# Dise_o_de_FISICA_v16.net
KiCad netlist of a schematic drawn in EAGLE
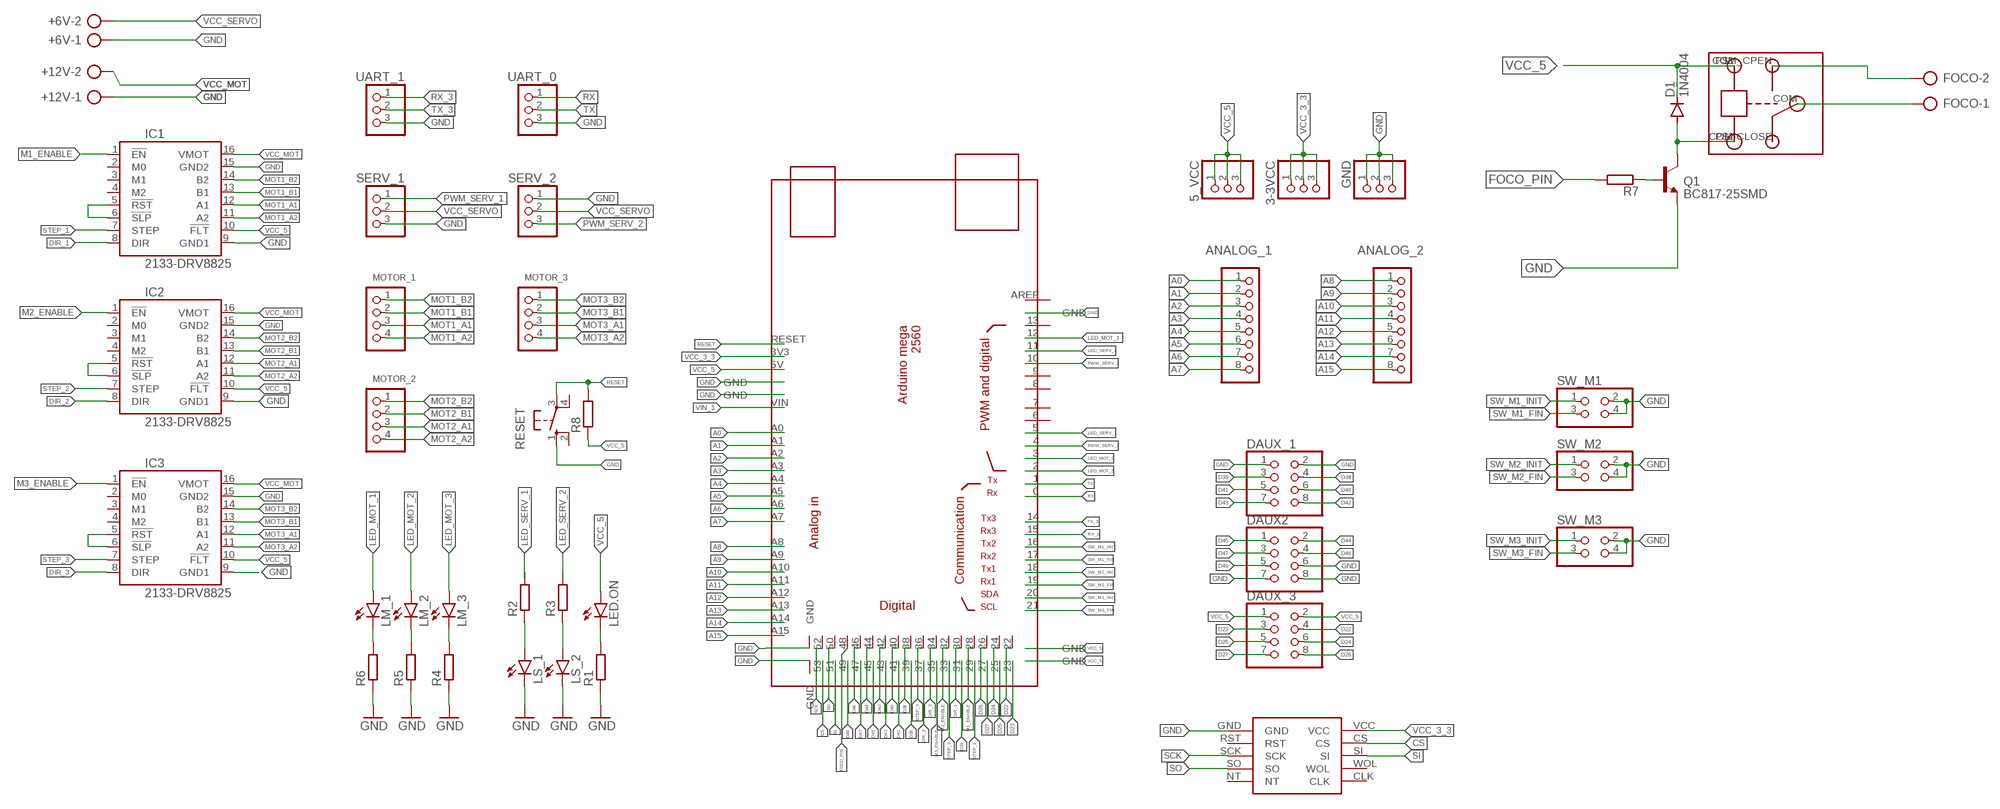
[diagram p0: schematic, sheet 1]

(export (version "E")
  (design (tool "Eeschema 10.0.6"))
  (components
    (comp (ref "+6V")
      (value "AK300/2")
      (footprint "eagle-import:AK300_2")
      (libsource (lib "eagle-import") (part "AK300/2"))
    )
    (comp (ref "+12V")
      (value "AK300/2")
      (footprint "eagle-import:AK300_2")
      (libsource (lib "eagle-import") (part "AK300/2"))
    )
    (comp (ref "3-3VCC")
      (value "PINHD-1X3")
      (footprint "eagle-import:1X03")
      (libsource (lib "eagle-import") (part "PINHD-1X3"))
    )
    (comp (ref "5_VCC")
      (value "PINHD-1X3")
      (footprint "eagle-import:1X03")
      (libsource (lib "eagle-import") (part "PINHD-1X3"))
    )
    (comp (ref "ANALOG_1")
      (value "PINHD-1X8")
      (footprint "eagle-import:1X08")
      (libsource (lib "eagle-import") (part "PINHD-1X8"))
    )
    (comp (ref "ANALOG_2")
      (value "PINHD-1X8")
      (footprint "eagle-import:1X08")
      (libsource (lib "eagle-import") (part "PINHD-1X8"))
    )
    (comp (ref "ARDUINOMEGA2560")
      (value "MEGA_DEVICE")
      (footprint "eagle-import:MEGAOUTLINE")
      (libsource (lib "eagle-import") (part "MEGA_DEVICE"))
    )
    (comp (ref "D1")
      (value "1N4004")
      (footprint "eagle-import:DO41-10")
      (libsource (lib "eagle-import") (part "1N4004"))
    )
    (comp (ref "DAUX2")
      (value "PINHD-2X4")
      (footprint "eagle-import:2X04")
      (libsource (lib "eagle-import") (part "PINHD-2X4"))
    )
    (comp (ref "DAUX_1")
      (value "PINHD-2X4")
      (footprint "eagle-import:2X04")
      (libsource (lib "eagle-import") (part "PINHD-2X4"))
    )
    (comp (ref "DAUX_3")
      (value "PINHD-2X4")
      (footprint "eagle-import:2X04")
      (libsource (lib "eagle-import") (part "PINHD-2X4"))
    )
    (comp (ref "FOCO")
      (value "AK300/2")
      (footprint "eagle-import:AK300_2")
      (libsource (lib "eagle-import") (part "AK300/2"))
    )
    (comp (ref "GND")
      (value "PINHD-1X3")
      (footprint "eagle-import:1X03")
      (libsource (lib "eagle-import") (part "PINHD-1X3"))
    )
    (comp (ref "IC1")
      (value "2133-DRV8825")
      (footprint "eagle-import:DRV8825")
      (libsource (lib "eagle-import") (part "2133-DRV8825"))
    )
    (comp (ref "IC2")
      (value "2133-DRV8825")
      (footprint "eagle-import:DRV8825")
      (libsource (lib "eagle-import") (part "2133-DRV8825"))
    )
    (comp (ref "IC3")
      (value "2133-DRV8825")
      (footprint "eagle-import:DRV8825")
      (libsource (lib "eagle-import") (part "2133-DRV8825"))
    )
    (comp (ref "LED.ON")
      (value "LED3MM")
      (footprint "eagle-import:LED3MM")
      (libsource (lib "eagle-import") (part "LED3MM"))
    )
    (comp (ref "LM_1")
      (value "LED3MM")
      (footprint "eagle-import:LED3MM")
      (libsource (lib "eagle-import") (part "LED3MM"))
    )
    (comp (ref "LM_2")
      (value "LED3MM")
      (footprint "eagle-import:LED3MM")
      (libsource (lib "eagle-import") (part "LED3MM"))
    )
    (comp (ref "LM_3")
      (value "LED3MM")
      (footprint "eagle-import:LED3MM")
      (libsource (lib "eagle-import") (part "LED3MM"))
    )
    (comp (ref "LS_1")
      (value "LED3MM")
      (footprint "eagle-import:LED3MM")
      (libsource (lib "eagle-import") (part "LED3MM"))
    )
    (comp (ref "LS_2")
      (value "LED3MM")
      (footprint "eagle-import:LED3MM")
      (libsource (lib "eagle-import") (part "LED3MM"))
    )
    (comp (ref "MODULO_ETHERNET")
      (value "ENC28J60")
      (footprint "eagle-import:ENC28J60")
      (libsource (lib "eagle-import") (part "ENC28J60"))
    )
    (comp (ref "MOTOR_1")
      (value "PINHD-1X4")
      (footprint "eagle-import:1X04")
      (libsource (lib "eagle-import") (part "PINHD-1X4"))
    )
    (comp (ref "MOTOR_2")
      (value "PINHD-1X4")
      (footprint "eagle-import:1X04")
      (libsource (lib "eagle-import") (part "PINHD-1X4"))
    )
    (comp (ref "MOTOR_3")
      (value "PINHD-1X4")
      (footprint "eagle-import:1X04")
      (libsource (lib "eagle-import") (part "PINHD-1X4"))
    )
    (comp (ref "Q1")
      (value "BC817-25SMD")
      (footprint "eagle-import:SOT23-BEC")
      (libsource (lib "eagle-import") (part "BC817SMD-25"))
    )
    (comp (ref "R1")
      (value "R_CHIP-0805(2012-METRIC)")
      (footprint "eagle-import:RESC2012X65")
      (libsource (lib "eagle-import") (part "RCHIP-0805(2012-METRIC)_"))
    )
    (comp (ref "R2")
      (value "R_CHIP-0805(2012-METRIC)")
      (footprint "eagle-import:RESC2012X65")
      (libsource (lib "eagle-import") (part "RCHIP-0805(2012-METRIC)_"))
    )
    (comp (ref "R3")
      (value "R_CHIP-0805(2012-METRIC)")
      (footprint "eagle-import:RESC2012X65")
      (libsource (lib "eagle-import") (part "RCHIP-0805(2012-METRIC)_"))
    )
    (comp (ref "R4")
      (value "R_CHIP-0805(2012-METRIC)")
      (footprint "eagle-import:RESC2012X65")
      (libsource (lib "eagle-import") (part "RCHIP-0805(2012-METRIC)_"))
    )
    (comp (ref "R5")
      (value "R_CHIP-0805(2012-METRIC)")
      (footprint "eagle-import:RESC2012X65")
      (libsource (lib "eagle-import") (part "RCHIP-0805(2012-METRIC)_"))
    )
    (comp (ref "R6")
      (value "R_CHIP-0805(2012-METRIC)")
      (footprint "eagle-import:RESC2012X65")
      (libsource (lib "eagle-import") (part "RCHIP-0805(2012-METRIC)_"))
    )
    (comp (ref "R7")
      (value "R_CHIP-0805(2012-METRIC)")
      (footprint "eagle-import:RESC2012X65")
      (libsource (lib "eagle-import") (part "RCHIP-0805(2012-METRIC)_"))
    )
    (comp (ref "R8")
      (value "R_CHIP-0805(2012-METRIC)")
      (footprint "eagle-import:RESC2012X65")
      (libsource (lib "eagle-import") (part "RCHIP-0805(2012-METRIC)_"))
    )
    (comp (ref "RESET")
      (value "10-XX")
      (footprint "eagle-import:B3F-10XX")
      (fields (field (name "MPN") "B3F-1000"))
      (libsource (lib "eagle-import") (part "10-XX"))
    )
    (comp (ref "SERV_1")
      (value "PINHD-1X3")
      (footprint "eagle-import:1X03")
      (libsource (lib "eagle-import") (part "PINHD-1X3"))
    )
    (comp (ref "SERV_2")
      (value "PINHD-1X3")
      (footprint "eagle-import:1X03")
      (libsource (lib "eagle-import") (part "PINHD-1X3"))
    )
    (comp (ref "SW_M1")
      (value "PINHD-2X2")
      (footprint "eagle-import:2X02")
      (libsource (lib "eagle-import") (part "PINHD-2X2"))
    )
    (comp (ref "SW_M2")
      (value "PINHD-2X2")
      (footprint "eagle-import:2X02")
      (libsource (lib "eagle-import") (part "PINHD-2X2"))
    )
    (comp (ref "SW_M3")
      (value "PINHD-2X2")
      (footprint "eagle-import:2X02")
      (libsource (lib "eagle-import") (part "PINHD-2X2"))
    )
    (comp (ref "U$1")
      (value "RELAY")
      (footprint "eagle-import:RELAY")
      (libsource (lib "eagle-import") (part "RELAY"))
    )
    (comp (ref "UART_0")
      (value "PINHD-1X3")
      (footprint "eagle-import:1X03")
      (libsource (lib "eagle-import") (part "PINHD-1X3"))
    )
    (comp (ref "UART_1")
      (value "PINHD-1X3")
      (footprint "eagle-import:1X03")
      (libsource (lib "eagle-import") (part "PINHD-1X3"))
    )
  )
  (nets
    (net (code "1") (name "A0") (class "Default")
      (node (ref "ANALOG_1") (pin "1") (pinfunction "1_1") (pintype "passive"))
      (node (ref "ARDUINOMEGA2560") (pin "A0") (pinfunction "A0_A0") (pintype "bidirectional"))
    )
    (net (code "2") (name "A1") (class "Default")
      (node (ref "ANALOG_1") (pin "2") (pinfunction "2_2") (pintype "passive"))
      (node (ref "ARDUINOMEGA2560") (pin "A1") (pinfunction "A1_A1") (pintype "bidirectional"))
    )
    (net (code "3") (name "A2") (class "Default")
      (node (ref "ANALOG_1") (pin "3") (pinfunction "3_3") (pintype "passive"))
      (node (ref "ARDUINOMEGA2560") (pin "A2") (pinfunction "A2_A2") (pintype "bidirectional"))
    )
    (net (code "4") (name "A3") (class "Default")
      (node (ref "ANALOG_1") (pin "4") (pinfunction "4_4") (pintype "passive"))
      (node (ref "ARDUINOMEGA2560") (pin "A3") (pinfunction "A3_A3") (pintype "bidirectional"))
    )
    (net (code "5") (name "A4") (class "Default")
      (node (ref "ANALOG_1") (pin "5") (pinfunction "5_5") (pintype "passive"))
      (node (ref "ARDUINOMEGA2560") (pin "A4") (pinfunction "A4_A4") (pintype "bidirectional"))
    )
    (net (code "6") (name "A5") (class "Default")
      (node (ref "ANALOG_1") (pin "6") (pinfunction "6_6") (pintype "passive"))
      (node (ref "ARDUINOMEGA2560") (pin "A5") (pinfunction "A5_A5") (pintype "bidirectional"))
    )
    (net (code "7") (name "A6") (class "Default")
      (node (ref "ANALOG_1") (pin "7") (pinfunction "7_7") (pintype "passive"))
      (node (ref "ARDUINOMEGA2560") (pin "A6") (pinfunction "A6_A6") (pintype "bidirectional"))
    )
    (net (code "8") (name "A7") (class "Default")
      (node (ref "ANALOG_1") (pin "8") (pinfunction "8_8") (pintype "passive"))
      (node (ref "ARDUINOMEGA2560") (pin "A7") (pinfunction "A7_A7") (pintype "bidirectional"))
    )
    (net (code "9") (name "A8") (class "Default")
      (node (ref "ANALOG_2") (pin "1") (pinfunction "1_1") (pintype "passive"))
      (node (ref "ARDUINOMEGA2560") (pin "A8") (pinfunction "A8_A8") (pintype "bidirectional"))
    )
    (net (code "10") (name "A9") (class "Default")
      (node (ref "ANALOG_2") (pin "2") (pinfunction "2_2") (pintype "passive"))
      (node (ref "ARDUINOMEGA2560") (pin "A9") (pinfunction "A9_A9") (pintype "bidirectional"))
    )
    (net (code "11") (name "A10") (class "Default")
      (node (ref "ANALOG_2") (pin "3") (pinfunction "3_3") (pintype "passive"))
      (node (ref "ARDUINOMEGA2560") (pin "A10") (pinfunction "A10_A10") (pintype "bidirectional"))
    )
    (net (code "12") (name "A11") (class "Default")
      (node (ref "ANALOG_2") (pin "4") (pinfunction "4_4") (pintype "passive"))
      (node (ref "ARDUINOMEGA2560") (pin "A11") (pinfunction "A11_A11") (pintype "bidirectional"))
    )
    (net (code "13") (name "A12") (class "Default")
      (node (ref "ANALOG_2") (pin "5") (pinfunction "5_5") (pintype "passive"))
      (node (ref "ARDUINOMEGA2560") (pin "A12") (pinfunction "A12_A12") (pintype "bidirectional"))
    )
    (net (code "14") (name "A13") (class "Default")
      (node (ref "ANALOG_2") (pin "6") (pinfunction "6_6") (pintype "passive"))
      (node (ref "ARDUINOMEGA2560") (pin "A13") (pinfunction "A13_A13") (pintype "bidirectional"))
    )
    (net (code "15") (name "A14") (class "Default")
      (node (ref "ANALOG_2") (pin "7") (pinfunction "7_7") (pintype "passive"))
      (node (ref "ARDUINOMEGA2560") (pin "A14") (pinfunction "A14_A14") (pintype "bidirectional"))
    )
    (net (code "16") (name "A15") (class "Default")
      (node (ref "ANALOG_2") (pin "8") (pinfunction "8_8") (pintype "passive"))
      (node (ref "ARDUINOMEGA2560") (pin "A15") (pinfunction "A15_A15") (pintype "bidirectional"))
    )
    (net (code "17") (name "CS") (class "Default")
      (node (ref "ARDUINOMEGA2560") (pin "53") (pinfunction "53_53") (pintype "bidirectional"))
      (node (ref "MODULO_ETHERNET") (pin "CS") (pinfunction "CS_CS") (pintype "bidirectional"))
    )
    (net (code "18") (name "D22") (class "Default")
      (node (ref "ARDUINOMEGA2560") (pin "22") (pinfunction "22_22") (pintype "bidirectional"))
      (node (ref "DAUX_3") (pin "4") (pinfunction "4_4") (pintype "passive"))
    )
    (net (code "19") (name "D23") (class "Default")
      (node (ref "ARDUINOMEGA2560") (pin "23") (pinfunction "23_23") (pintype "bidirectional"))
      (node (ref "DAUX_3") (pin "3") (pinfunction "3_3") (pintype "passive"))
    )
    (net (code "20") (name "D24") (class "Default")
      (node (ref "ARDUINOMEGA2560") (pin "24") (pinfunction "24_24") (pintype "bidirectional"))
      (node (ref "DAUX_3") (pin "6") (pinfunction "6_6") (pintype "passive"))
    )
    (net (code "21") (name "D25") (class "Default")
      (node (ref "ARDUINOMEGA2560") (pin "25") (pinfunction "25_25") (pintype "bidirectional"))
      (node (ref "DAUX_3") (pin "5") (pinfunction "5_5") (pintype "passive"))
    )
    (net (code "22") (name "D26") (class "Default")
      (node (ref "ARDUINOMEGA2560") (pin "26") (pinfunction "26_26") (pintype "bidirectional"))
      (node (ref "DAUX_3") (pin "8") (pinfunction "8_8") (pintype "passive"))
    )
    (net (code "23") (name "D27") (class "Default")
      (node (ref "ARDUINOMEGA2560") (pin "27") (pinfunction "27_27") (pintype "bidirectional"))
      (node (ref "DAUX_3") (pin "7") (pinfunction "7_7") (pintype "passive"))
    )
    (net (code "24") (name "D31") (class "Default")
      (node (ref "ARDUINOMEGA2560") (pin "31") (pinfunction "31_31") (pintype "bidirectional"))
    )
    (net (code "25") (name "D38") (class "Default")
      (node (ref "ARDUINOMEGA2560") (pin "38") (pinfunction "38_38") (pintype "bidirectional"))
      (node (ref "DAUX_1") (pin "4") (pinfunction "4_4") (pintype "passive"))
    )
    (net (code "26") (name "D39") (class "Default")
      (node (ref "ARDUINOMEGA2560") (pin "39") (pinfunction "39_39") (pintype "bidirectional"))
      (node (ref "DAUX_1") (pin "3") (pinfunction "3_3") (pintype "passive"))
    )
    (net (code "27") (name "D40") (class "Default")
      (node (ref "ARDUINOMEGA2560") (pin "40") (pinfunction "40_40") (pintype "bidirectional"))
      (node (ref "DAUX_1") (pin "6") (pinfunction "6_6") (pintype "passive"))
    )
    (net (code "28") (name "D41") (class "Default")
      (node (ref "ARDUINOMEGA2560") (pin "41") (pinfunction "41_41") (pintype "bidirectional"))
      (node (ref "DAUX_1") (pin "5") (pinfunction "5_5") (pintype "passive"))
    )
    (net (code "29") (name "D42") (class "Default")
      (node (ref "ARDUINOMEGA2560") (pin "42") (pinfunction "42_42") (pintype "bidirectional"))
      (node (ref "DAUX_1") (pin "8") (pinfunction "8_8") (pintype "passive"))
    )
    (net (code "30") (name "D43") (class "Default")
      (node (ref "ARDUINOMEGA2560") (pin "43") (pinfunction "43_43") (pintype "bidirectional"))
      (node (ref "DAUX_1") (pin "7") (pinfunction "7_7") (pintype "passive"))
    )
    (net (code "31") (name "D44") (class "Default")
      (node (ref "ARDUINOMEGA2560") (pin "44") (pinfunction "44_44") (pintype "bidirectional"))
      (node (ref "DAUX2") (pin "2") (pinfunction "2_2") (pintype "passive"))
    )
    (net (code "32") (name "D45") (class "Default")
      (node (ref "ARDUINOMEGA2560") (pin "45") (pinfunction "45_45") (pintype "bidirectional"))
      (node (ref "DAUX2") (pin "1") (pinfunction "1_1") (pintype "passive"))
    )
    (net (code "33") (name "D46") (class "Default")
      (node (ref "ARDUINOMEGA2560") (pin "46") (pinfunction "46_46") (pintype "bidirectional"))
      (node (ref "DAUX2") (pin "4") (pinfunction "4_4") (pintype "passive"))
    )
    (net (code "34") (name "D47") (class "Default")
      (node (ref "ARDUINOMEGA2560") (pin "47") (pinfunction "47_47") (pintype "bidirectional"))
      (node (ref "DAUX2") (pin "3") (pinfunction "3_3") (pintype "passive"))
    )
    (net (code "35") (name "D49") (class "Default")
      (node (ref "ARDUINOMEGA2560") (pin "49") (pinfunction "49_49") (pintype "bidirectional"))
      (node (ref "DAUX2") (pin "5") (pinfunction "5_5") (pintype "passive"))
    )
    (net (code "36") (name "DIR_1") (class "Default")
      (node (ref "ARDUINOMEGA2560") (pin "30") (pinfunction "30_30") (pintype "bidirectional"))
      (node (ref "IC1") (pin "8") (pinfunction "DIR_8") (pintype "input"))
    )
    (net (code "37") (name "DIR_2") (class "Default")
      (node (ref "ARDUINOMEGA2560") (pin "34") (pinfunction "34_34") (pintype "bidirectional"))
      (node (ref "IC2") (pin "8") (pinfunction "DIR_8") (pintype "input"))
    )
    (net (code "38") (name "DIR_3") (class "Default")
      (node (ref "ARDUINOMEGA2560") (pin "37") (pinfunction "37_37") (pintype "bidirectional"))
      (node (ref "IC3") (pin "8") (pinfunction "DIR_8") (pintype "input"))
    )
    (net (code "39") (name "FOCO_PIN") (class "Default")
      (node (ref "ARDUINOMEGA2560") (pin "48") (pinfunction "48_48") (pintype "bidirectional"))
      (node (ref "R7") (pin "2") (pinfunction "2_2") (pintype "passive"))
    )
    (net (code "40") (name "GND") (class "Default")
      (node (ref "+12V") (pin "1") (pinfunction "KL_1") (pintype "passive"))
      (node (ref "+6V") (pin "1") (pinfunction "KL_1") (pintype "passive"))
      (node (ref "ARDUINOMEGA2560") (pin "GND@1") (pinfunction "GND_GND@1") (pintype "bidirectional"))
      (node (ref "ARDUINOMEGA2560") (pin "GND@2") (pinfunction "GND_GND@2") (pintype "bidirectional"))
      (node (ref "ARDUINOMEGA2560") (pin "GND@3") (pinfunction "GND_GND@3") (pintype "bidirectional"))
      (node (ref "ARDUINOMEGA2560") (pin "GND@6") (pinfunction "GND_GND@6") (pintype "bidirectional"))
      (node (ref "ARDUINOMEGA2560") (pin "GND@7") (pinfunction "GND_GND@7") (pintype "bidirectional"))
      (node (ref "DAUX2") (pin "6") (pinfunction "6_6") (pintype "passive"))
      (node (ref "DAUX2") (pin "7") (pinfunction "7_7") (pintype "passive"))
      (node (ref "DAUX2") (pin "8") (pinfunction "8_8") (pintype "passive"))
      (node (ref "DAUX_1") (pin "1") (pinfunction "1_1") (pintype "passive"))
      (node (ref "DAUX_1") (pin "2") (pinfunction "2_2") (pintype "passive"))
      (node (ref "GND") (pin "1") (pinfunction "1_1") (pintype "passive"))
      (node (ref "GND") (pin "2") (pinfunction "2_2") (pintype "passive"))
      (node (ref "GND") (pin "3") (pinfunction "3_3") (pintype "passive"))
      (node (ref "IC1") (pin "15") (pinfunction "GND2_15") (pintype "power_in"))
      (node (ref "IC1") (pin "9") (pinfunction "GND1_9") (pintype "power_in"))
      (node (ref "IC2") (pin "15") (pinfunction "GND2_15") (pintype "power_in"))
      (node (ref "IC2") (pin "9") (pinfunction "GND1_9") (pintype "power_in"))
      (node (ref "IC3") (pin "15") (pinfunction "GND2_15") (pintype "power_in"))
      (node (ref "IC3") (pin "9") (pinfunction "GND1_9") (pintype "power_in"))
      (node (ref "LS_1") (pin "K") (pinfunction "C_K") (pintype "passive"))
      (node (ref "LS_2") (pin "K") (pinfunction "C_K") (pintype "passive"))
      (node (ref "MODULO_ETHERNET") (pin "GND") (pinfunction "GND_GND") (pintype "bidirectional"))
      (node (ref "Q1") (pin "E") (pinfunction "E_E") (pintype "passive"))
      (node (ref "R1") (pin "1") (pinfunction "1_1") (pintype "passive"))
      (node (ref "R4") (pin "1") (pinfunction "1_1") (pintype "passive"))
      (node (ref "R5") (pin "1") (pinfunction "1_1") (pintype "passive"))
      (node (ref "R6") (pin "1") (pinfunction "1_1") (pintype "passive"))
      (node (ref "RESET") (pin "1") (pinfunction "S_1") (pintype "passive"))
      (node (ref "SERV_1") (pin "3") (pinfunction "3_3") (pintype "passive"))
      (node (ref "SERV_2") (pin "1") (pinfunction "1_1") (pintype "passive"))
      (node (ref "SW_M1") (pin "2") (pinfunction "2_2") (pintype "passive"))
      (node (ref "SW_M1") (pin "4") (pinfunction "4_4") (pintype "passive"))
      (node (ref "SW_M2") (pin "2") (pinfunction "2_2") (pintype "passive"))
      (node (ref "SW_M2") (pin "4") (pinfunction "4_4") (pintype "passive"))
      (node (ref "SW_M3") (pin "2") (pinfunction "2_2") (pintype "passive"))
      (node (ref "SW_M3") (pin "4") (pinfunction "4_4") (pintype "passive"))
      (node (ref "UART_0") (pin "3") (pinfunction "3_3") (pintype "passive"))
      (node (ref "UART_1") (pin "3") (pinfunction "3_3") (pintype "passive"))
    )
    (net (code "41") (name "LED_MOT_1") (class "Default")
      (node (ref "ARDUINOMEGA2560") (pin "12") (pinfunction "12_12") (pintype "bidirectional"))
      (node (ref "LM_1") (pin "A") (pinfunction "A_A") (pintype "passive"))
    )
    (net (code "42") (name "LED_MOT_2") (class "Default")
      (node (ref "ARDUINOMEGA2560") (pin "3") (pinfunction "3_3") (pintype "bidirectional"))
      (node (ref "LM_2") (pin "A") (pinfunction "A_A") (pintype "passive"))
    )
    (net (code "43") (name "LED_MOT_3") (class "Default")
      (node (ref "ARDUINOMEGA2560") (pin "2") (pinfunction "2_2") (pintype "bidirectional"))
      (node (ref "LM_3") (pin "A") (pinfunction "A_A") (pintype "passive"))
    )
    (net (code "44") (name "LED_SERV_1") (class "Default")
      (node (ref "ARDUINOMEGA2560") (pin "5") (pinfunction "5_5") (pintype "bidirectional"))
      (node (ref "R2") (pin "2") (pinfunction "2_2") (pintype "passive"))
    )
    (net (code "45") (name "LED_SERV_2") (class "Default")
      (node (ref "ARDUINOMEGA2560") (pin "11") (pinfunction "11_11") (pintype "bidirectional"))
      (node (ref "R3") (pin "2") (pinfunction "2_2") (pintype "passive"))
    )
    (net (code "46") (name "M1_ENABLE") (class "Default")
      (node (ref "ARDUINOMEGA2560") (pin "28") (pinfunction "28_28") (pintype "bidirectional"))
      (node (ref "IC1") (pin "1") (pinfunction "~{EN}_1") (pintype "passive"))
    )
    (net (code "47") (name "M2_ENABLE") (class "Default")
      (node (ref "ARDUINOMEGA2560") (pin "32") (pinfunction "32_32") (pintype "bidirectional"))
      (node (ref "IC2") (pin "1") (pinfunction "~{EN}_1") (pintype "passive"))
    )
    (net (code "48") (name "M3_ENABLE") (class "Default")
      (node (ref "ARDUINOMEGA2560") (pin "35") (pinfunction "35_35") (pintype "bidirectional"))
      (node (ref "IC3") (pin "1") (pinfunction "~{EN}_1") (pintype "passive"))
    )
    (net (code "49") (name "MOT1_A1") (class "Default")
      (node (ref "IC1") (pin "12") (pinfunction "A1_12") (pintype "output"))
      (node (ref "MOTOR_1") (pin "3") (pinfunction "3_3") (pintype "passive"))
    )
    (net (code "50") (name "MOT1_A2") (class "Default")
      (node (ref "IC1") (pin "11") (pinfunction "A2_11") (pintype "output"))
      (node (ref "MOTOR_1") (pin "4") (pinfunction "4_4") (pintype "passive"))
    )
    (net (code "51") (name "MOT1_B1") (class "Default")
      (node (ref "IC1") (pin "13") (pinfunction "B1_13") (pintype "output"))
      (node (ref "MOTOR_1") (pin "2") (pinfunction "2_2") (pintype "passive"))
    )
    (net (code "52") (name "MOT1_B2") (class "Default")
      (node (ref "IC1") (pin "14") (pinfunction "B2_14") (pintype "output"))
      (node (ref "MOTOR_1") (pin "1") (pinfunction "1_1") (pintype "passive"))
    )
    (net (code "53") (name "MOT2_A1") (class "Default")
      (node (ref "IC2") (pin "12") (pinfunction "A1_12") (pintype "output"))
      (node (ref "MOTOR_2") (pin "3") (pinfunction "3_3") (pintype "passive"))
    )
    (net (code "54") (name "MOT2_A2") (class "Default")
      (node (ref "IC2") (pin "11") (pinfunction "A2_11") (pintype "output"))
      (node (ref "MOTOR_2") (pin "4") (pinfunction "4_4") (pintype "passive"))
    )
    (net (code "55") (name "MOT2_B1") (class "Default")
      (node (ref "IC2") (pin "13") (pinfunction "B1_13") (pintype "output"))
      (node (ref "MOTOR_2") (pin "2") (pinfunction "2_2") (pintype "passive"))
    )
    (net (code "56") (name "MOT2_B2") (class "Default")
      (node (ref "IC2") (pin "14") (pinfunction "B2_14") (pintype "output"))
      (node (ref "MOTOR_2") (pin "1") (pinfunction "1_1") (pintype "passive"))
    )
    (net (code "57") (name "MOT3_A1") (class "Default")
      (node (ref "IC3") (pin "12") (pinfunction "A1_12") (pintype "output"))
      (node (ref "MOTOR_3") (pin "3") (pinfunction "3_3") (pintype "passive"))
    )
    (net (code "58") (name "MOT3_A2") (class "Default")
      (node (ref "IC3") (pin "11") (pinfunction "A2_11") (pintype "output"))
      (node (ref "MOTOR_3") (pin "4") (pinfunction "4_4") (pintype "passive"))
    )
    (net (code "59") (name "MOT3_B1") (class "Default")
      (node (ref "IC3") (pin "13") (pinfunction "B1_13") (pintype "output"))
      (node (ref "MOTOR_3") (pin "2") (pinfunction "2_2") (pintype "passive"))
    )
    (net (code "60") (name "MOT3_B2") (class "Default")
      (node (ref "IC3") (pin "14") (pinfunction "B2_14") (pintype "output"))
      (node (ref "MOTOR_3") (pin "1") (pinfunction "1_1") (pintype "passive"))
    )
    (net (code "61") (name "Net-(FOCOA-KL)") (class "Default")
      (node (ref "FOCO") (pin "1") (pinfunction "KL_1") (pintype "passive"))
      (node (ref "U$1") (pin "COM") (pinfunction "COM_COM") (pintype "bidirectional"))
    )
    (net (code "62") (name "Net-(FOCOB-KL)") (class "Default")
      (node (ref "FOCO") (pin "2") (pinfunction "KL_2") (pintype "passive"))
      (node (ref "U$1") (pin "COM_CPEN") (pinfunction "COM-OPEN_COM_CPEN") (pintype "bidirectional"))
    )
    (net (code "63") (name "Net-(IC1-~{RST})") (class "Default")
      (node (ref "IC1") (pin "5") (pinfunction "~{RST}_5") (pintype "input"))
      (node (ref "IC1") (pin "6") (pinfunction "~{SLP}_6") (pintype "input"))
    )
    (net (code "64") (name "Net-(IC2-~{RST})") (class "Default")
      (node (ref "IC2") (pin "5") (pinfunction "~{RST}_5") (pintype "input"))
      (node (ref "IC2") (pin "6") (pinfunction "~{SLP}_6") (pintype "input"))
    )
    (net (code "65") (name "Net-(IC3-~{RST})") (class "Default")
      (node (ref "IC3") (pin "5") (pinfunction "~{RST}_5") (pintype "input"))
      (node (ref "IC3") (pin "6") (pinfunction "~{SLP}_6") (pintype "input"))
    )
    (net (code "66") (name "Net-(LED.ON-C)") (class "Default")
      (node (ref "LED.ON") (pin "K") (pinfunction "C_K") (pintype "passive"))
      (node (ref "R1") (pin "2") (pinfunction "2_2") (pintype "passive"))
    )
    (net (code "67") (name "Net-(LM_1-C)") (class "Default")
      (node (ref "LM_1") (pin "K") (pinfunction "C_K") (pintype "passive"))
      (node (ref "R6") (pin "2") (pinfunction "2_2") (pintype "passive"))
    )
    (net (code "68") (name "Net-(LM_2-C)") (class "Default")
      (node (ref "LM_2") (pin "K") (pinfunction "C_K") (pintype "passive"))
      (node (ref "R5") (pin "2") (pinfunction "2_2") (pintype "passive"))
    )
    (net (code "69") (name "Net-(LM_3-C)") (class "Default")
      (node (ref "LM_3") (pin "K") (pinfunction "C_K") (pintype "passive"))
      (node (ref "R4") (pin "2") (pinfunction "2_2") (pintype "passive"))
    )
    (net (code "70") (name "Net-(LS_1-PadA)") (class "Default")
      (node (ref "LS_1") (pin "A") (pinfunction "A_A") (pintype "passive"))
      (node (ref "R2") (pin "1") (pinfunction "1_1") (pintype "passive"))
    )
    (net (code "71") (name "Net-(LS_2-PadA)") (class "Default")
      (node (ref "LS_2") (pin "A") (pinfunction "A_A") (pintype "passive"))
      (node (ref "R3") (pin "1") (pinfunction "1_1") (pintype "passive"))
    )
    (net (code "72") (name "Net-(Q1-PadB)") (class "Default")
      (node (ref "Q1") (pin "B") (pinfunction "B_B") (pintype "passive"))
      (node (ref "R7") (pin "1") (pinfunction "1_1") (pintype "passive"))
    )
    (net (code "73") (name "Net-(U$1-GND)") (class "Default")
      (node (ref "D1") (pin "A") (pinfunction "A_A") (pintype "passive"))
      (node (ref "Q1") (pin "C") (pinfunction "C_C") (pintype "passive"))
      (node (ref "U$1") (pin "P$2") (pinfunction "GND_P$2") (pintype "bidirectional"))
    )
    (net (code "74") (name "PWM_SERV_1") (class "Default")
      (node (ref "ARDUINOMEGA2560") (pin "4") (pinfunction "4_4") (pintype "bidirectional"))
      (node (ref "SERV_1") (pin "1") (pinfunction "1_1") (pintype "passive"))
    )
    (net (code "75") (name "PWM_SERV_2") (class "Default")
      (node (ref "ARDUINOMEGA2560") (pin "10") (pinfunction "10_10") (pintype "bidirectional"))
      (node (ref "SERV_2") (pin "3") (pinfunction "3_3") (pintype "passive"))
    )
    (net (code "76") (name "RESET") (class "Default")
      (node (ref "ARDUINOMEGA2560") (pin "RESET") (pinfunction "RESET_RESET") (pintype "bidirectional"))
      (node (ref "R8") (pin "2") (pinfunction "2_2") (pintype "passive"))
      (node (ref "RESET") (pin "3") (pinfunction "P_3") (pintype "passive"))
    )
    (net (code "77") (name "RX") (class "Default")
      (node (ref "ARDUINOMEGA2560") (pin "0") (pinfunction "0_0") (pintype "bidirectional"))
      (node (ref "UART_0") (pin "1") (pinfunction "1_1") (pintype "passive"))
    )
    (net (code "78") (name "RX_3") (class "Default")
      (node (ref "ARDUINOMEGA2560") (pin "15") (pinfunction "15_15") (pintype "bidirectional"))
      (node (ref "UART_1") (pin "1") (pinfunction "1_1") (pintype "passive"))
    )
    (net (code "79") (name "SCK") (class "Default")
      (node (ref "ARDUINOMEGA2560") (pin "52") (pinfunction "52_52") (pintype "bidirectional"))
      (node (ref "MODULO_ETHERNET") (pin "SCK") (pinfunction "SCK_SCK") (pintype "bidirectional"))
    )
    (net (code "80") (name "SI") (class "Default")
      (node (ref "ARDUINOMEGA2560") (pin "51") (pinfunction "51_51") (pintype "bidirectional"))
      (node (ref "MODULO_ETHERNET") (pin "SI") (pinfunction "SI_SI") (pintype "bidirectional"))
    )
    (net (code "81") (name "SO") (class "Default")
      (node (ref "ARDUINOMEGA2560") (pin "50") (pinfunction "50_50") (pintype "bidirectional"))
      (node (ref "MODULO_ETHERNET") (pin "SO") (pinfunction "SO_SO") (pintype "bidirectional"))
    )
    (net (code "82") (name "STEP_1") (class "Default")
      (node (ref "ARDUINOMEGA2560") (pin "29") (pinfunction "29_29") (pintype "bidirectional"))
      (node (ref "IC1") (pin "7") (pinfunction "STEP_7") (pintype "input"))
    )
    (net (code "83") (name "STEP_2") (class "Default")
      (node (ref "ARDUINOMEGA2560") (pin "33") (pinfunction "33_33") (pintype "bidirectional"))
      (node (ref "IC2") (pin "7") (pinfunction "STEP_7") (pintype "input"))
    )
    (net (code "84") (name "STEP_3") (class "Default")
      (node (ref "ARDUINOMEGA2560") (pin "36") (pinfunction "36_36") (pintype "bidirectional"))
      (node (ref "IC3") (pin "7") (pinfunction "STEP_7") (pintype "input"))
    )
    (net (code "85") (name "SW_M1_FIN") (class "Default")
      (node (ref "ARDUINOMEGA2560") (pin "17") (pinfunction "17_17") (pintype "bidirectional"))
      (node (ref "SW_M1") (pin "3") (pinfunction "3_3") (pintype "passive"))
    )
    (net (code "86") (name "SW_M1_INIT") (class "Default")
      (node (ref "ARDUINOMEGA2560") (pin "16") (pinfunction "16_16") (pintype "bidirectional"))
      (node (ref "SW_M1") (pin "1") (pinfunction "1_1") (pintype "passive"))
    )
    (net (code "87") (name "SW_M2_FIN") (class "Default")
      (node (ref "ARDUINOMEGA2560") (pin "19") (pinfunction "19_19") (pintype "bidirectional"))
      (node (ref "SW_M2") (pin "3") (pinfunction "3_3") (pintype "passive"))
    )
    (net (code "88") (name "SW_M2_INIT") (class "Default")
      (node (ref "ARDUINOMEGA2560") (pin "18") (pinfunction "18_18") (pintype "bidirectional"))
      (node (ref "SW_M2") (pin "1") (pinfunction "1_1") (pintype "passive"))
    )
    (net (code "89") (name "SW_M3_FIN") (class "Default")
      (node (ref "ARDUINOMEGA2560") (pin "21") (pinfunction "21_21") (pintype "bidirectional"))
      (node (ref "SW_M3") (pin "3") (pinfunction "3_3") (pintype "passive"))
    )
    (net (code "90") (name "SW_M3_INIT") (class "Default")
      (node (ref "ARDUINOMEGA2560") (pin "20") (pinfunction "20_20") (pintype "bidirectional"))
      (node (ref "SW_M3") (pin "1") (pinfunction "1_1") (pintype "passive"))
    )
    (net (code "91") (name "TX") (class "Default")
      (node (ref "ARDUINOMEGA2560") (pin "1") (pinfunction "1_1") (pintype "bidirectional"))
      (node (ref "UART_0") (pin "2") (pinfunction "2_2") (pintype "passive"))
    )
    (net (code "92") (name "TX_3") (class "Default")
      (node (ref "ARDUINOMEGA2560") (pin "14") (pinfunction "14_14") (pintype "bidirectional"))
      (node (ref "UART_1") (pin "2") (pinfunction "2_2") (pintype "passive"))
    )
    (net (code "93") (name "VCC_3_3") (class "Default")
      (node (ref "3-3VCC") (pin "1") (pinfunction "1_1") (pintype "passive"))
      (node (ref "3-3VCC") (pin "2") (pinfunction "2_2") (pintype "passive"))
      (node (ref "3-3VCC") (pin "3") (pinfunction "3_3") (pintype "passive"))
      (node (ref "ARDUINOMEGA2560") (pin "3V3") (pinfunction "3V3_3V3") (pintype "bidirectional"))
      (node (ref "MODULO_ETHERNET") (pin "VCC") (pinfunction "VCC_VCC") (pintype "bidirectional"))
    )
    (net (code "94") (name "VCC_5") (class "Default")
      (node (ref "5_VCC") (pin "1") (pinfunction "1_1") (pintype "passive"))
      (node (ref "5_VCC") (pin "2") (pinfunction "2_2") (pintype "passive"))
      (node (ref "5_VCC") (pin "3") (pinfunction "3_3") (pintype "passive"))
      (node (ref "ARDUINOMEGA2560") (pin "5V") (pinfunction "5V_5V") (pintype "bidirectional"))
      (node (ref "ARDUINOMEGA2560") (pin "GND@4") (pinfunction "GND_GND@4") (pintype "bidirectional"))
      (node (ref "ARDUINOMEGA2560") (pin "GND@5") (pinfunction "GND_GND@5") (pintype "bidirectional"))
      (node (ref "D1") (pin "C") (pinfunction "C_C") (pintype "passive"))
      (node (ref "DAUX_3") (pin "1") (pinfunction "1_1") (pintype "passive"))
      (node (ref "DAUX_3") (pin "2") (pinfunction "2_2") (pintype "passive"))
      (node (ref "IC1") (pin "10") (pinfunction "~{FLT}_10") (pintype "open_collector"))
      (node (ref "IC2") (pin "10") (pinfunction "~{FLT}_10") (pintype "open_collector"))
      (node (ref "IC3") (pin "10") (pinfunction "~{FLT}_10") (pintype "open_collector"))
      (node (ref "LED.ON") (pin "A") (pinfunction "A_A") (pintype "passive"))
      (node (ref "R8") (pin "1") (pinfunction "1_1") (pintype "passive"))
      (node (ref "U$1") (pin "P$1") (pinfunction "IN_P$1") (pintype "bidirectional"))
    )
    (net (code "95") (name "VCC_MOT") (class "Default")
      (node (ref "+12V") (pin "2") (pinfunction "KL_2") (pintype "passive"))
      (node (ref "IC1") (pin "16") (pinfunction "VMOT_16") (pintype "power_in"))
      (node (ref "IC2") (pin "16") (pinfunction "VMOT_16") (pintype "power_in"))
      (node (ref "IC3") (pin "16") (pinfunction "VMOT_16") (pintype "power_in"))
    )
    (net (code "96") (name "VCC_SERVO") (class "Default")
      (node (ref "+6V") (pin "2") (pinfunction "KL_2") (pintype "passive"))
      (node (ref "SERV_1") (pin "2") (pinfunction "2_2") (pintype "passive"))
      (node (ref "SERV_2") (pin "2") (pinfunction "2_2") (pintype "passive"))
    )
    (net (code "97") (name "VIN_1") (class "Default")
      (node (ref "ARDUINOMEGA2560") (pin "VIN") (pinfunction "VIN_VIN") (pintype "bidirectional"))
    )
    (net (code "98") (name "unconnected-(ARDUINOMEGA2560-Pad6)") (class "Default")
      (node (ref "ARDUINOMEGA2560") (pin "6") (pinfunction "6_6") (pintype "bidirectional"))
    )
    (net (code "99") (name "unconnected-(ARDUINOMEGA2560-Pad7)") (class "Default")
      (node (ref "ARDUINOMEGA2560") (pin "7") (pinfunction "7_7") (pintype "bidirectional"))
    )
    (net (code "100") (name "unconnected-(ARDUINOMEGA2560-Pad8)") (class "Default")
      (node (ref "ARDUINOMEGA2560") (pin "8") (pinfunction "8_8") (pintype "bidirectional"))
    )
    (net (code "101") (name "unconnected-(ARDUINOMEGA2560-Pad9)") (class "Default")
      (node (ref "ARDUINOMEGA2560") (pin "9") (pinfunction "9_9") (pintype "bidirectional"))
    )
    (net (code "102") (name "unconnected-(ARDUINOMEGA2560-Pad13)") (class "Default")
      (node (ref "ARDUINOMEGA2560") (pin "13") (pinfunction "13_13") (pintype "bidirectional"))
    )
    (net (code "103") (name "unconnected-(ARDUINOMEGA2560-PadAREF)") (class "Default")
      (node (ref "ARDUINOMEGA2560") (pin "AREF") (pinfunction "AREF_AREF") (pintype "bidirectional"))
    )
    (net (code "104") (name "unconnected-(IC1-M0-Pad2)") (class "Default")
      (node (ref "IC1") (pin "2") (pinfunction "M0_2") (pintype "passive"))
    )
    (net (code "105") (name "unconnected-(IC1-M1-Pad3)") (class "Default")
      (node (ref "IC1") (pin "3") (pinfunction "M1_3") (pintype "passive"))
    )
    (net (code "106") (name "unconnected-(IC1-M2-Pad4)") (class "Default")
      (node (ref "IC1") (pin "4") (pinfunction "M2_4") (pintype "passive"))
    )
    (net (code "107") (name "unconnected-(IC2-M0-Pad2)") (class "Default")
      (node (ref "IC2") (pin "2") (pinfunction "M0_2") (pintype "passive"))
    )
    (net (code "108") (name "unconnected-(IC2-M1-Pad3)") (class "Default")
      (node (ref "IC2") (pin "3") (pinfunction "M1_3") (pintype "passive"))
    )
    (net (code "109") (name "unconnected-(IC2-M2-Pad4)") (class "Default")
      (node (ref "IC2") (pin "4") (pinfunction "M2_4") (pintype "passive"))
    )
    (net (code "110") (name "unconnected-(IC3-M0-Pad2)") (class "Default")
      (node (ref "IC3") (pin "2") (pinfunction "M0_2") (pintype "passive"))
    )
    (net (code "111") (name "unconnected-(IC3-M1-Pad3)") (class "Default")
      (node (ref "IC3") (pin "3") (pinfunction "M1_3") (pintype "passive"))
    )
    (net (code "112") (name "unconnected-(IC3-M2-Pad4)") (class "Default")
      (node (ref "IC3") (pin "4") (pinfunction "M2_4") (pintype "passive"))
    )
    (net (code "113") (name "unconnected-(MODULO_ETHERNET-PadCLK)") (class "Default")
      (node (ref "MODULO_ETHERNET") (pin "CLK") (pinfunction "CLK_CLK") (pintype "bidirectional"))
    )
    (net (code "114") (name "unconnected-(MODULO_ETHERNET-PadNT)") (class "Default")
      (node (ref "MODULO_ETHERNET") (pin "NT") (pinfunction "NT_NT") (pintype "bidirectional"))
    )
    (net (code "115") (name "unconnected-(MODULO_ETHERNET-PadRST)") (class "Default")
      (node (ref "MODULO_ETHERNET") (pin "RST") (pinfunction "RST_RST") (pintype "bidirectional"))
    )
    (net (code "116") (name "unconnected-(MODULO_ETHERNET-PadWOL)") (class "Default")
      (node (ref "MODULO_ETHERNET") (pin "WOL") (pinfunction "WOL_WOL") (pintype "bidirectional"))
    )
    (net (code "117") (name "unconnected-(RESET-P1-Pad4)") (class "Default")
      (node (ref "RESET") (pin "4") (pinfunction "P1_4") (pintype "passive"))
    )
    (net (code "118") (name "unconnected-(RESET-S1-Pad2)") (class "Default")
      (node (ref "RESET") (pin "2") (pinfunction "S1_2") (pintype "passive"))
    )
    (net (code "119") (name "unconnected-(U$1-PadCOM-CLOSE)") (class "Default")
      (node (ref "U$1") (pin "COM-CLOSE") (pinfunction "COM-CLOSE_COM-CLOSE") (pintype "bidirectional"))
    )
  )
)
